# Gagabiro_power_supply_maida.net
KiCad netlist of a schematic drawn in Altium Designer
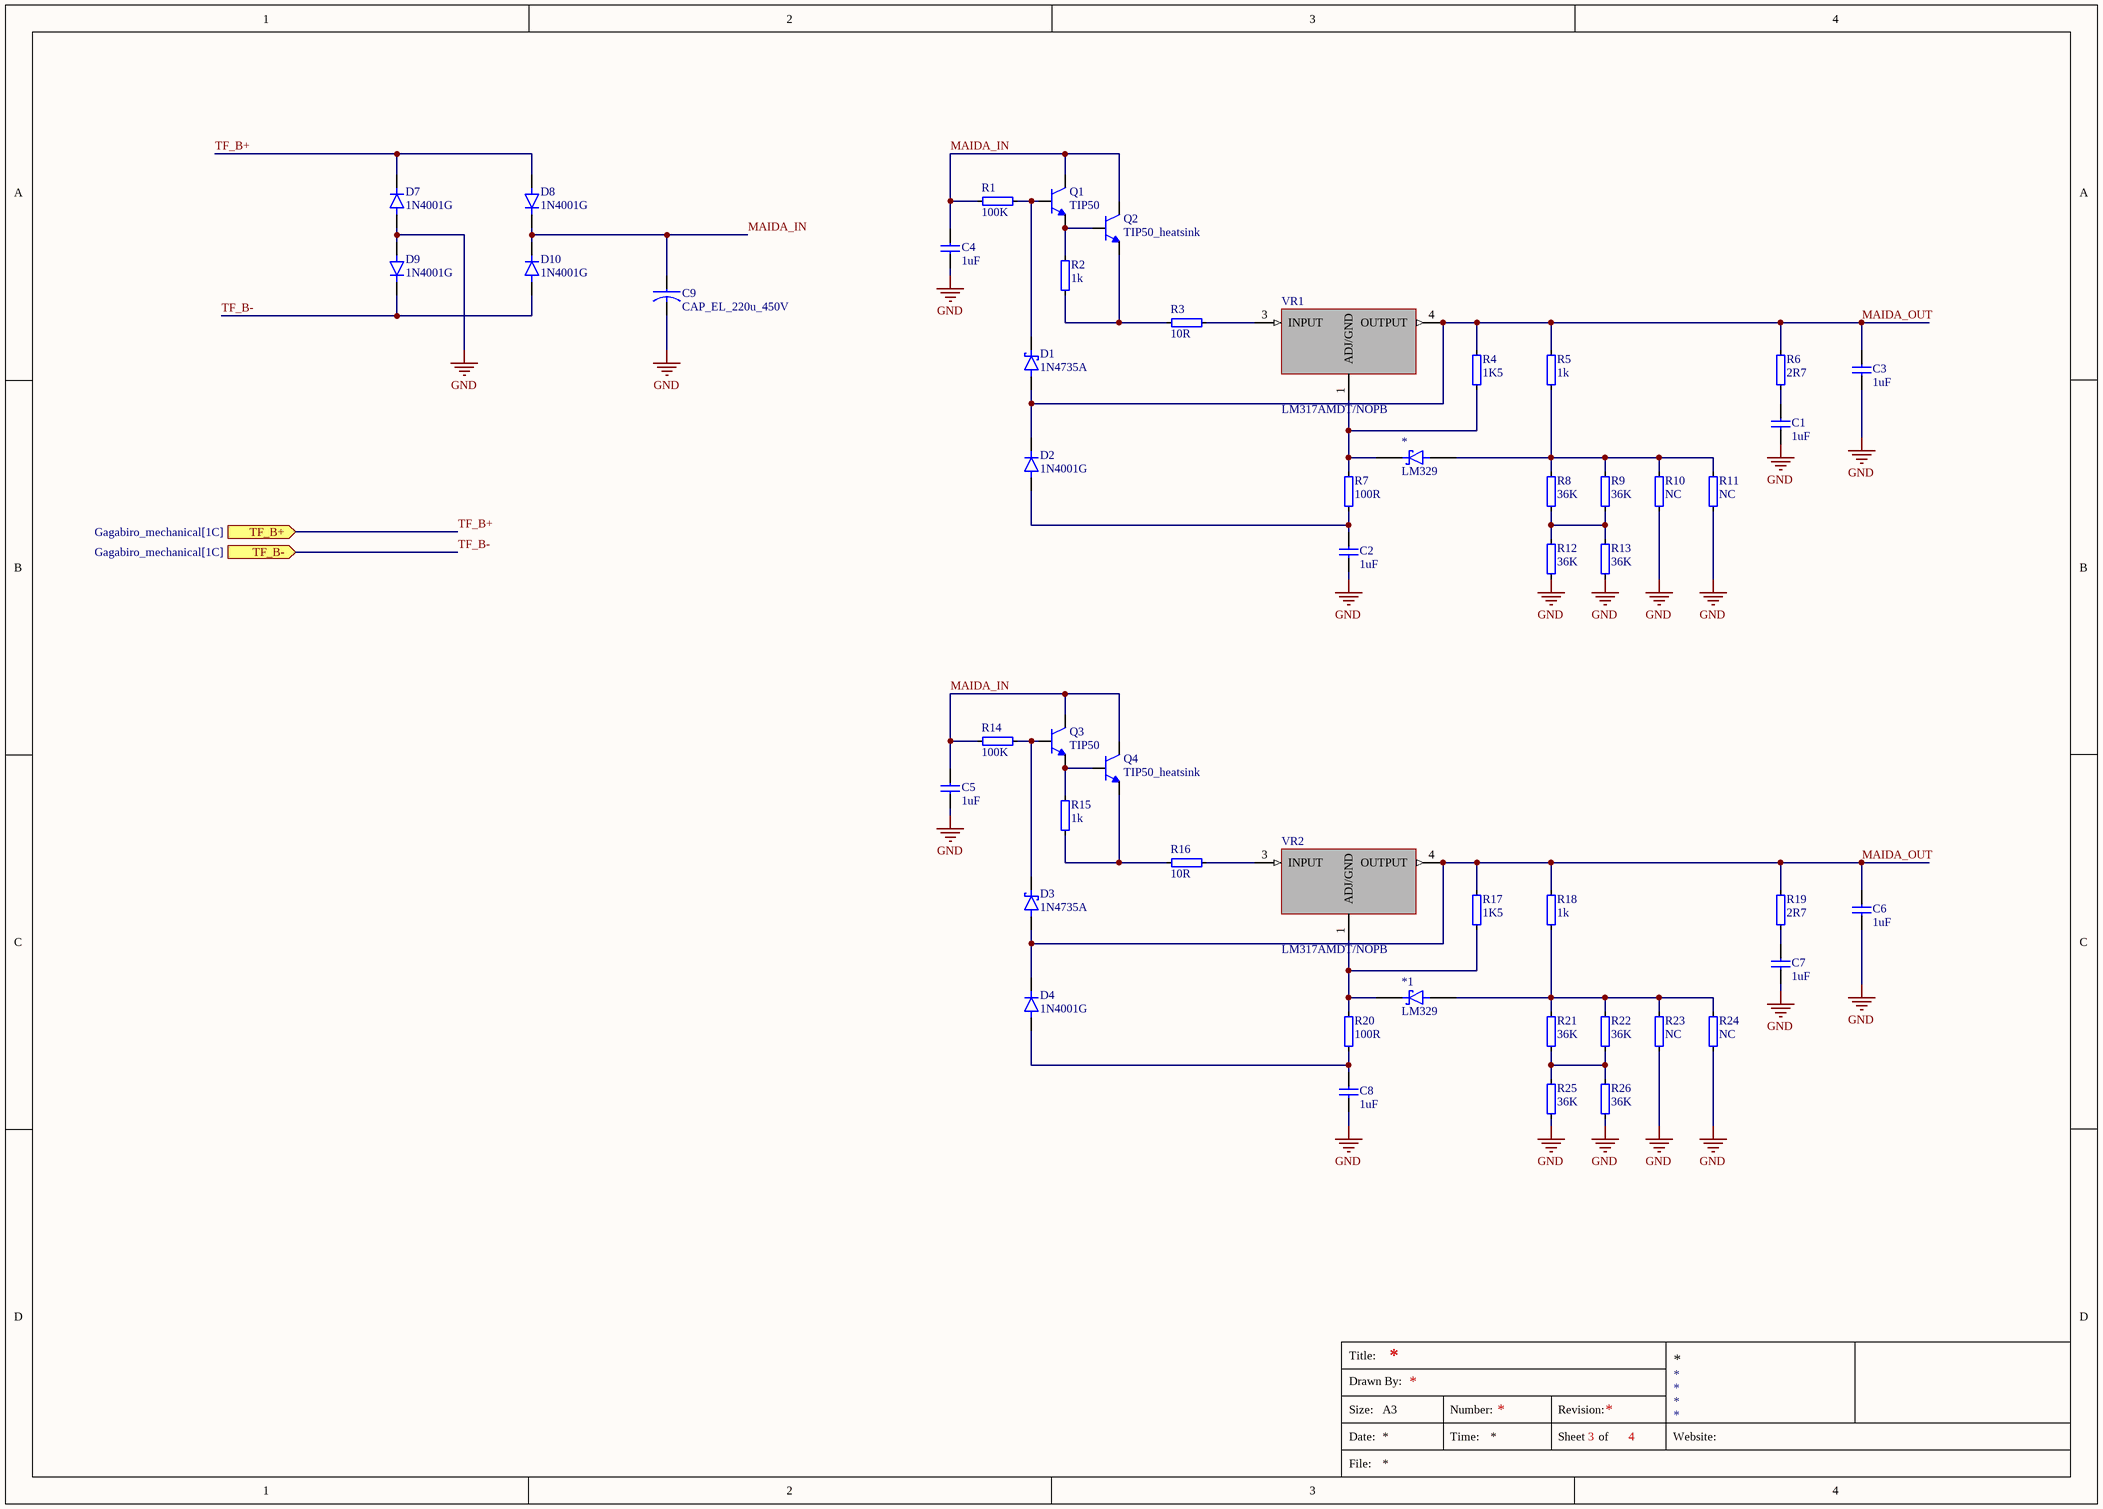
[diagram p0: Gagabiro_power_supply_maida.SchDoc]

(export (version "E")
  (design (tool "Eeschema 10.0.6"))
  (components
    (comp (ref "*")
      (value "LM329")
      (footprint "TO92127P495H495-3")
      (libsource (lib "Persephone_Integrated_Library") (part "LM329"))
    )
    (comp (ref "*1")
      (value "LM329")
      (footprint "TO92127P495H495-3")
      (libsource (lib "Persephone_Integrated_Library") (part "LM329"))
    )
    (comp (ref "C1")
      (value "1uF")
      (footprint "CAP_panassonic_1u_450V")
      (description "Capacitor, Silver Mica")
      (fields (field (name "PART NUMBER") "CMICA_47PF"))
      (libsource (lib "Persephone_Integrated_Library") (part "CAP_POLY_1u"))
    )
    (comp (ref "C2")
      (value "1uF")
      (footprint "CAP_panassonic_1u_450V")
      (description "Capacitor, Silver Mica")
      (fields (field (name "PART NUMBER") "CMICA_47PF"))
      (libsource (lib "Persephone_Integrated_Library") (part "CAP_POLY_1u"))
    )
    (comp (ref "C3")
      (value "1uF")
      (footprint "CAP_panassonic_1u_450V")
      (description "Capacitor, Silver Mica")
      (fields (field (name "PART NUMBER") "CMICA_47PF"))
      (libsource (lib "Persephone_Integrated_Library") (part "CAP_POLY_1u"))
    )
    (comp (ref "C4")
      (value "1uF")
      (footprint "CAP_panassonic_1u_450V")
      (description "Capacitor, Silver Mica")
      (fields (field (name "PART NUMBER") "CMICA_47PF"))
      (libsource (lib "Persephone_Integrated_Library") (part "CAP_POLY_1u"))
    )
    (comp (ref "C5")
      (value "1uF")
      (footprint "CAP_panassonic_1u_450V")
      (description "Capacitor, Silver Mica")
      (fields (field (name "PART NUMBER") "CMICA_47PF"))
      (libsource (lib "Persephone_Integrated_Library") (part "CAP_POLY_1u"))
    )
    (comp (ref "C6")
      (value "1uF")
      (footprint "CAP_panassonic_1u_450V")
      (description "Capacitor, Silver Mica")
      (fields (field (name "PART NUMBER") "CMICA_47PF"))
      (libsource (lib "Persephone_Integrated_Library") (part "CAP_POLY_1u"))
    )
    (comp (ref "C7")
      (value "1uF")
      (footprint "CAP_panassonic_1u_450V")
      (description "Capacitor, Silver Mica")
      (fields (field (name "PART NUMBER") "CMICA_47PF"))
      (libsource (lib "Persephone_Integrated_Library") (part "CAP_POLY_1u"))
    )
    (comp (ref "C8")
      (value "1uF")
      (footprint "CAP_panassonic_1u_450V")
      (description "Capacitor, Silver Mica")
      (fields (field (name "PART NUMBER") "CMICA_47PF"))
      (libsource (lib "Persephone_Integrated_Library") (part "CAP_POLY_1u"))
    )
    (comp (ref "C9")
      (value "CAP_EL_220u_450V")
      (footprint "CAPPRD500W50D630H1120_stand_25x50")
      (description "220F 16V Aluminum Electrolytic Capacitors Radial, Can 1000 Hrs @ 105C")
      (fields (field (name "MP") "EEU-HD1C221B") (field (name "MF") "Panasonic"))
      (libsource (lib "Persephone_Integrated_Library") (part "CAP_EL_220u_450V"))
    )
    (comp (ref "D1")
      (value "1N4735A")
      (footprint "DIOAD1036W78L463D272")
      (description "Zener Diode 6.2V 1W Â±5% Through Hole DO-204AL (DO-41)")
      (fields (field (name "MF") "ON Semiconductor"))
      (libsource (lib "Persephone_Integrated_Library") (part "1N4735A"))
    )
    (comp (ref "D2")
      (value "1N4001G")
      (footprint "DIOAD1036W78L470D235")
      (description "1A, 50V, Standard Recovery Rectifier")
      (fields (field (name "MF") "Taiwan Semiconductor"))
      (libsource (lib "Persephone_Integrated_Library") (part "1N4001G"))
    )
    (comp (ref "D3")
      (value "1N4735A")
      (footprint "DIOAD1036W78L463D272")
      (description "Zener Diode 6.2V 1W Â±5% Through Hole DO-204AL (DO-41)")
      (fields (field (name "MF") "ON Semiconductor"))
      (libsource (lib "Persephone_Integrated_Library") (part "1N4735A"))
    )
    (comp (ref "D4")
      (value "1N4001G")
      (footprint "DIOAD1036W78L470D235")
      (description "1A, 50V, Standard Recovery Rectifier")
      (fields (field (name "MF") "Taiwan Semiconductor"))
      (libsource (lib "Persephone_Integrated_Library") (part "1N4001G"))
    )
    (comp (ref "D7")
      (value "1N4001G")
      (footprint "DIOAD1036W78L470D235")
      (description "1A, 50V, Standard Recovery Rectifier")
      (fields (field (name "MF") "Taiwan Semiconductor"))
      (libsource (lib "Persephone_Integrated_Library") (part "1N4001G"))
    )
    (comp (ref "D8")
      (value "1N4001G")
      (footprint "DIOAD1036W78L470D235")
      (description "1A, 50V, Standard Recovery Rectifier")
      (fields (field (name "MF") "Taiwan Semiconductor"))
      (libsource (lib "Persephone_Integrated_Library") (part "1N4001G"))
    )
    (comp (ref "D9")
      (value "1N4001G")
      (footprint "DIOAD1036W78L470D235")
      (description "1A, 50V, Standard Recovery Rectifier")
      (fields (field (name "MF") "Taiwan Semiconductor"))
      (libsource (lib "Persephone_Integrated_Library") (part "1N4001G"))
    )
    (comp (ref "D10")
      (value "1N4001G")
      (footprint "DIOAD1036W78L470D235")
      (description "1A, 50V, Standard Recovery Rectifier")
      (fields (field (name "MF") "Taiwan Semiconductor"))
      (libsource (lib "Persephone_Integrated_Library") (part "1N4001G"))
    )
    (comp (ref "Q1")
      (value "TIP50")
      (footprint "TO254P1009X445X1985-3")
      (description "Bipolar (BJT) Transistor NPN 400 V 1 A 10MHz 2 W Through Hole TO-220-3")
      (fields (field (name "MF") "ON Semiconductor"))
      (libsource (lib "Persephone_Integrated_Library") (part "TIP50"))
    )
    (comp (ref "Q2")
      (value "TIP50_heatsink")
      (footprint "TO254P1009X445X1985-3_heatsink")
      (description "Bipolar (BJT) Transistor NPN 400 V 1 A 10MHz 2 W Through Hole TO-220-3")
      (fields (field (name "MF") "ON Semiconductor") (field (name "MP") "TIP50"))
      (libsource (lib "Persephone_Integrated_Library") (part "TIP50_heatsink"))
    )
    (comp (ref "Q3")
      (value "TIP50")
      (footprint "TO254P1009X445X1985-3")
      (description "Bipolar (BJT) Transistor NPN 400 V 1 A 10MHz 2 W Through Hole TO-220-3")
      (fields (field (name "MF") "ON Semiconductor"))
      (libsource (lib "Persephone_Integrated_Library") (part "TIP50"))
    )
    (comp (ref "Q4")
      (value "TIP50_heatsink")
      (footprint "TO254P1009X445X1985-3_heatsink")
      (description "Bipolar (BJT) Transistor NPN 400 V 1 A 10MHz 2 W Through Hole TO-220-3")
      (fields (field (name "MF") "ON Semiconductor") (field (name "MP") "TIP50"))
      (libsource (lib "Persephone_Integrated_Library") (part "TIP50_heatsink"))
    )
    (comp (ref "R1")
      (value "100K")
      (footprint "RES_2W_vertical")
      (description "Resistor, 2W")
      (fields (field (name "PART NUMBER") "R2W") (field (name "AUTHOR") "colombari"))
      (libsource (lib "Persephone_Integrated_Library") (part "R_2W_vertical_100K"))
    )
    (comp (ref "R2")
      (value "1k")
      (footprint "RES_2W_vertical")
      (description "Resistor, 2W")
      (fields (field (name "PART NUMBER") "R2W") (field (name "AUTHOR") "colombari"))
      (libsource (lib "Persephone_Integrated_Library") (part "R_2W_vertical_1k"))
    )
    (comp (ref "R3")
      (value "10R")
      (footprint "RES_2W_vertical")
      (description "Resistor, 2W")
      (fields (field (name "PART NUMBER") "R2W") (field (name "AUTHOR") "colombari"))
      (libsource (lib "Persephone_Integrated_Library") (part "R_2W_vertical_10R"))
    )
    (comp (ref "R4")
      (value "1K5")
      (footprint "RES_2W_vertical")
      (description "Resistor, 2W")
      (fields (field (name "PART NUMBER") "R2W") (field (name "AUTHOR") "colombari"))
      (libsource (lib "Persephone_Integrated_Library") (part "R_2W_vertical_1K5"))
    )
    (comp (ref "R5")
      (value "1k")
      (footprint "RES_2W_vertical")
      (description "Resistor, 2W")
      (fields (field (name "PART NUMBER") "R2W") (field (name "AUTHOR") "colombari"))
      (libsource (lib "Persephone_Integrated_Library") (part "R_2W_vertical_1k"))
    )
    (comp (ref "R6")
      (value "2R7")
      (footprint "RES_2W_vertical")
      (description "Resistor, 2W")
      (fields (field (name "PART NUMBER") "R2W") (field (name "AUTHOR") "colombari"))
      (libsource (lib "Persephone_Integrated_Library") (part "R_2W_vertical_2R7"))
    )
    (comp (ref "R7")
      (value "100R")
      (footprint "RES_2W_vertical")
      (description "Resistor, 2W")
      (fields (field (name "PART NUMBER") "R2W") (field (name "AUTHOR") "colombari"))
      (libsource (lib "Persephone_Integrated_Library") (part "R_2W_vertical_100R"))
    )
    (comp (ref "R8")
      (value "36K")
      (footprint "RES_2W_vertical")
      (description "Resistor, 2W")
      (fields (field (name "PART NUMBER") "R2W") (field (name "AUTHOR") "colombari"))
      (libsource (lib "Persephone_Integrated_Library") (part "R_2W_vertical_36K"))
    )
    (comp (ref "R9")
      (value "36K")
      (footprint "RES_2W_vertical")
      (description "Resistor, 2W")
      (fields (field (name "PART NUMBER") "R2W") (field (name "AUTHOR") "colombari"))
      (libsource (lib "Persephone_Integrated_Library") (part "R_2W_vertical_36K"))
    )
    (comp (ref "R10")
      (value "NC")
      (footprint "RES_2W_vertical")
      (description "Resistor, 2W")
      (fields (field (name "PART NUMBER") "R2W") (field (name "AUTHOR") "colombari"))
      (libsource (lib "Persephone_Integrated_Library") (part "R_2W_vertical_NC"))
    )
    (comp (ref "R11")
      (value "NC")
      (footprint "RES_2W_vertical")
      (description "Resistor, 2W")
      (fields (field (name "PART NUMBER") "R2W") (field (name "AUTHOR") "colombari"))
      (libsource (lib "Persephone_Integrated_Library") (part "R_2W_vertical_NC"))
    )
    (comp (ref "R12")
      (value "36K")
      (footprint "RES_2W_vertical")
      (description "Resistor, 2W")
      (fields (field (name "PART NUMBER") "R2W") (field (name "AUTHOR") "colombari"))
      (libsource (lib "Persephone_Integrated_Library") (part "R_2W_vertical_36K"))
    )
    (comp (ref "R13")
      (value "36K")
      (footprint "RES_2W_vertical")
      (description "Resistor, 2W")
      (fields (field (name "PART NUMBER") "R2W") (field (name "AUTHOR") "colombari"))
      (libsource (lib "Persephone_Integrated_Library") (part "R_2W_vertical_36K"))
    )
    (comp (ref "R14")
      (value "100K")
      (footprint "RES_2W_vertical")
      (description "Resistor, 2W")
      (fields (field (name "PART NUMBER") "R2W") (field (name "AUTHOR") "colombari"))
      (libsource (lib "Persephone_Integrated_Library") (part "R_2W_vertical_100K"))
    )
    (comp (ref "R15")
      (value "1k")
      (footprint "RES_2W_vertical")
      (description "Resistor, 2W")
      (fields (field (name "PART NUMBER") "R2W") (field (name "AUTHOR") "colombari"))
      (libsource (lib "Persephone_Integrated_Library") (part "R_2W_vertical_1k"))
    )
    (comp (ref "R16")
      (value "10R")
      (footprint "RES_2W_vertical")
      (description "Resistor, 2W")
      (fields (field (name "PART NUMBER") "R2W") (field (name "AUTHOR") "colombari"))
      (libsource (lib "Persephone_Integrated_Library") (part "R_2W_vertical_10R"))
    )
    (comp (ref "R17")
      (value "1K5")
      (footprint "RES_2W_vertical")
      (description "Resistor, 2W")
      (fields (field (name "PART NUMBER") "R2W") (field (name "AUTHOR") "colombari"))
      (libsource (lib "Persephone_Integrated_Library") (part "R_2W_vertical_1K5"))
    )
    (comp (ref "R18")
      (value "1k")
      (footprint "RES_2W_vertical")
      (description "Resistor, 2W")
      (fields (field (name "PART NUMBER") "R2W") (field (name "AUTHOR") "colombari"))
      (libsource (lib "Persephone_Integrated_Library") (part "R_2W_vertical_1k"))
    )
    (comp (ref "R19")
      (value "2R7")
      (footprint "RES_2W_vertical")
      (description "Resistor, 2W")
      (fields (field (name "PART NUMBER") "R2W") (field (name "AUTHOR") "colombari"))
      (libsource (lib "Persephone_Integrated_Library") (part "R_2W_vertical_2R7"))
    )
    (comp (ref "R20")
      (value "100R")
      (footprint "RES_2W_vertical")
      (description "Resistor, 2W")
      (fields (field (name "PART NUMBER") "R2W") (field (name "AUTHOR") "colombari"))
      (libsource (lib "Persephone_Integrated_Library") (part "R_2W_vertical_100R"))
    )
    (comp (ref "R21")
      (value "36K")
      (footprint "RES_2W_vertical")
      (description "Resistor, 2W")
      (fields (field (name "PART NUMBER") "R2W") (field (name "AUTHOR") "colombari"))
      (libsource (lib "Persephone_Integrated_Library") (part "R_2W_vertical_36K"))
    )
    (comp (ref "R22")
      (value "36K")
      (footprint "RES_2W_vertical")
      (description "Resistor, 2W")
      (fields (field (name "PART NUMBER") "R2W") (field (name "AUTHOR") "colombari"))
      (libsource (lib "Persephone_Integrated_Library") (part "R_2W_vertical_36K"))
    )
    (comp (ref "R23")
      (value "NC")
      (footprint "RES_2W_vertical")
      (description "Resistor, 2W")
      (fields (field (name "PART NUMBER") "R2W") (field (name "AUTHOR") "colombari"))
      (libsource (lib "Persephone_Integrated_Library") (part "R_2W_vertical_NC"))
    )
    (comp (ref "R24")
      (value "NC")
      (footprint "RES_2W_vertical")
      (description "Resistor, 2W")
      (fields (field (name "PART NUMBER") "R2W") (field (name "AUTHOR") "colombari"))
      (libsource (lib "Persephone_Integrated_Library") (part "R_2W_vertical_NC"))
    )
    (comp (ref "R25")
      (value "36K")
      (footprint "RES_2W_vertical")
      (description "Resistor, 2W")
      (fields (field (name "PART NUMBER") "R2W") (field (name "AUTHOR") "colombari"))
      (libsource (lib "Persephone_Integrated_Library") (part "R_2W_vertical_36K"))
    )
    (comp (ref "R26")
      (value "36K")
      (footprint "RES_2W_vertical")
      (description "Resistor, 2W")
      (fields (field (name "PART NUMBER") "R2W") (field (name "AUTHOR") "colombari"))
      (libsource (lib "Persephone_Integrated_Library") (part "R_2W_vertical_36K"))
    )
    (comp (ref "VR1")
      (value "LM317AMDT/NOPB")
      (footprint "TO228P991X255-3N")
      (libsource (lib "Persephone_Integrated_Library") (part "LM317AMDT/NOPB"))
    )
    (comp (ref "VR2")
      (value "LM317AMDT/NOPB")
      (footprint "TO228P991X255-3N")
      (libsource (lib "Persephone_Integrated_Library") (part "LM317AMDT/NOPB"))
    )
  )
  (nets
    (net (code "1") (name "/MAIDA_IN") (class "Default")
      (node (ref "C4") (pin "2") (pinfunction "2_2") (pintype "passive"))
      (node (ref "C5") (pin "2") (pinfunction "2_2") (pintype "passive"))
      (node (ref "C9") (pin "P") (pinfunction "P_P") (pintype "passive"))
      (node (ref "D10") (pin "C") (pinfunction "K_C") (pintype "passive"))
      (node (ref "D8") (pin "C") (pinfunction "K_C") (pintype "passive"))
      (node (ref "Q1") (pin "2") (pinfunction "C_2") (pintype "passive"))
      (node (ref "Q2") (pin "2") (pinfunction "C_2") (pintype "passive"))
      (node (ref "Q3") (pin "2") (pinfunction "C_2") (pintype "passive"))
      (node (ref "Q4") (pin "2") (pinfunction "C_2") (pintype "passive"))
      (node (ref "R1") (pin "1") (pinfunction "1_1") (pintype "passive"))
      (node (ref "R14") (pin "1") (pinfunction "1_1") (pintype "passive"))
    )
    (net (code "2") (name "/MAIDA_OUT") (class "Default")
      (node (ref "C3") (pin "2") (pinfunction "2_2") (pintype "passive"))
      (node (ref "C6") (pin "2") (pinfunction "2_2") (pintype "passive"))
      (node (ref "D1") (pin "2") (pinfunction "A_2") (pintype "passive"))
      (node (ref "D2") (pin "C") (pinfunction "K_C") (pintype "passive"))
      (node (ref "D3") (pin "2") (pinfunction "A_2") (pintype "passive"))
      (node (ref "D4") (pin "C") (pinfunction "K_C") (pintype "passive"))
      (node (ref "R17") (pin "2") (pinfunction "2_2") (pintype "passive"))
      (node (ref "R18") (pin "2") (pinfunction "2_2") (pintype "passive"))
      (node (ref "R19") (pin "2") (pinfunction "2_2") (pintype "passive"))
      (node (ref "R4") (pin "2") (pinfunction "2_2") (pintype "passive"))
      (node (ref "R5") (pin "2") (pinfunction "2_2") (pintype "passive"))
      (node (ref "R6") (pin "2") (pinfunction "2_2") (pintype "passive"))
      (node (ref "VR1") (pin "4") (pinfunction "OUTPUT_4") (pintype "output"))
      (node (ref "VR2") (pin "4") (pinfunction "OUTPUT_4") (pintype "output"))
    )
    (net (code "3") (name "/TF_B+") (class "Default")
      (node (ref "D7") (pin "C") (pinfunction "K_C") (pintype "passive"))
      (node (ref "D8") (pin "A") (pinfunction "A_A") (pintype "passive"))
    )
    (net (code "4") (name "/TF_B-") (class "Default")
      (node (ref "D10") (pin "A") (pinfunction "A_A") (pintype "passive"))
      (node (ref "D9") (pin "C") (pinfunction "K_C") (pintype "passive"))
    )
    (net (code "5") (name "GND") (class "Default")
      (node (ref "C1") (pin "1") (pinfunction "1_1") (pintype "passive"))
      (node (ref "C2") (pin "1") (pinfunction "1_1") (pintype "passive"))
      (node (ref "C3") (pin "1") (pinfunction "1_1") (pintype "passive"))
      (node (ref "C4") (pin "1") (pinfunction "1_1") (pintype "passive"))
      (node (ref "C5") (pin "1") (pinfunction "1_1") (pintype "passive"))
      (node (ref "C6") (pin "1") (pinfunction "1_1") (pintype "passive"))
      (node (ref "C7") (pin "1") (pinfunction "1_1") (pintype "passive"))
      (node (ref "C8") (pin "1") (pinfunction "1_1") (pintype "passive"))
      (node (ref "C9") (pin "N") (pinfunction "N_N") (pintype "passive"))
      (node (ref "D7") (pin "A") (pinfunction "A_A") (pintype "passive"))
      (node (ref "D9") (pin "A") (pinfunction "A_A") (pintype "passive"))
      (node (ref "R10") (pin "1") (pinfunction "1_1") (pintype "passive"))
      (node (ref "R11") (pin "1") (pinfunction "1_1") (pintype "passive"))
      (node (ref "R12") (pin "1") (pinfunction "1_1") (pintype "passive"))
      (node (ref "R13") (pin "1") (pinfunction "1_1") (pintype "passive"))
      (node (ref "R23") (pin "1") (pinfunction "1_1") (pintype "passive"))
      (node (ref "R24") (pin "1") (pinfunction "1_1") (pintype "passive"))
      (node (ref "R25") (pin "1") (pinfunction "1_1") (pintype "passive"))
      (node (ref "R26") (pin "1") (pinfunction "1_1") (pintype "passive"))
    )
    (net (code "6") (name "Net-(*-Pad3)") (class "Default")
      (node (ref "*") (pin "3") (pinfunction "3_3") (pintype "power_in"))
      (node (ref "R10") (pin "2") (pinfunction "2_2") (pintype "passive"))
      (node (ref "R11") (pin "2") (pinfunction "2_2") (pintype "passive"))
      (node (ref "R5") (pin "1") (pinfunction "1_1") (pintype "passive"))
      (node (ref "R8") (pin "2") (pinfunction "2_2") (pintype "passive"))
      (node (ref "R9") (pin "2") (pinfunction "2_2") (pintype "passive"))
    )
    (net (code "7") (name "Net-(*1-Pad3)") (class "Default")
      (node (ref "*1") (pin "3") (pinfunction "3_3") (pintype "power_in"))
      (node (ref "R18") (pin "1") (pinfunction "1_1") (pintype "passive"))
      (node (ref "R21") (pin "2") (pinfunction "2_2") (pintype "passive"))
      (node (ref "R22") (pin "2") (pinfunction "2_2") (pintype "passive"))
      (node (ref "R23") (pin "2") (pinfunction "2_2") (pintype "passive"))
      (node (ref "R24") (pin "2") (pinfunction "2_2") (pintype "passive"))
    )
    (net (code "8") (name "Net-(C1-Pad2)") (class "Default")
      (node (ref "C1") (pin "2") (pinfunction "2_2") (pintype "passive"))
      (node (ref "R6") (pin "1") (pinfunction "1_1") (pintype "passive"))
    )
    (net (code "9") (name "Net-(C2-Pad2)") (class "Default")
      (node (ref "C2") (pin "2") (pinfunction "2_2") (pintype "passive"))
      (node (ref "D2") (pin "A") (pinfunction "A_A") (pintype "passive"))
      (node (ref "R7") (pin "1") (pinfunction "1_1") (pintype "passive"))
    )
    (net (code "10") (name "Net-(C7-Pad2)") (class "Default")
      (node (ref "C7") (pin "2") (pinfunction "2_2") (pintype "passive"))
      (node (ref "R19") (pin "1") (pinfunction "1_1") (pintype "passive"))
    )
    (net (code "11") (name "Net-(C8-Pad2)") (class "Default")
      (node (ref "C8") (pin "2") (pinfunction "2_2") (pintype "passive"))
      (node (ref "D4") (pin "A") (pinfunction "A_A") (pintype "passive"))
      (node (ref "R20") (pin "1") (pinfunction "1_1") (pintype "passive"))
    )
    (net (code "12") (name "Net-(D1-K)") (class "Default")
      (node (ref "D1") (pin "1") (pinfunction "K_1") (pintype "passive"))
      (node (ref "Q1") (pin "1") (pinfunction "B_1") (pintype "passive"))
      (node (ref "R1") (pin "2") (pinfunction "2_2") (pintype "passive"))
    )
    (net (code "13") (name "Net-(D3-K)") (class "Default")
      (node (ref "D3") (pin "1") (pinfunction "K_1") (pintype "passive"))
      (node (ref "Q3") (pin "1") (pinfunction "B_1") (pintype "passive"))
      (node (ref "R14") (pin "2") (pinfunction "2_2") (pintype "passive"))
    )
    (net (code "14") (name "Net-(Q1-E)") (class "Default")
      (node (ref "Q1") (pin "3") (pinfunction "E_3") (pintype "passive"))
      (node (ref "Q2") (pin "1") (pinfunction "B_1") (pintype "passive"))
      (node (ref "R2") (pin "2") (pinfunction "2_2") (pintype "passive"))
    )
    (net (code "15") (name "Net-(Q2-E)") (class "Default")
      (node (ref "Q2") (pin "3") (pinfunction "E_3") (pintype "passive"))
      (node (ref "R2") (pin "1") (pinfunction "1_1") (pintype "passive"))
      (node (ref "R3") (pin "2") (pinfunction "2_2") (pintype "passive"))
    )
    (net (code "16") (name "Net-(Q3-E)") (class "Default")
      (node (ref "Q3") (pin "3") (pinfunction "E_3") (pintype "passive"))
      (node (ref "Q4") (pin "1") (pinfunction "B_1") (pintype "passive"))
      (node (ref "R15") (pin "2") (pinfunction "2_2") (pintype "passive"))
    )
    (net (code "17") (name "Net-(Q4-E)") (class "Default")
      (node (ref "Q4") (pin "3") (pinfunction "E_3") (pintype "passive"))
      (node (ref "R15") (pin "1") (pinfunction "1_1") (pintype "passive"))
      (node (ref "R16") (pin "2") (pinfunction "2_2") (pintype "passive"))
    )
    (net (code "18") (name "Net-(R12-Pad2)") (class "Default")
      (node (ref "R12") (pin "2") (pinfunction "2_2") (pintype "passive"))
      (node (ref "R13") (pin "2") (pinfunction "2_2") (pintype "passive"))
      (node (ref "R8") (pin "1") (pinfunction "1_1") (pintype "passive"))
      (node (ref "R9") (pin "1") (pinfunction "1_1") (pintype "passive"))
    )
    (net (code "19") (name "Net-(R21-Pad1)") (class "Default")
      (node (ref "R21") (pin "1") (pinfunction "1_1") (pintype "passive"))
      (node (ref "R22") (pin "1") (pinfunction "1_1") (pintype "passive"))
      (node (ref "R25") (pin "2") (pinfunction "2_2") (pintype "passive"))
      (node (ref "R26") (pin "2") (pinfunction "2_2") (pintype "passive"))
    )
    (net (code "20") (name "Net-(VR1-ADJ{slash}GND)") (class "Default")
      (node (ref "*") (pin "2") (pinfunction "2_2") (pintype "power_in"))
      (node (ref "R4") (pin "1") (pinfunction "1_1") (pintype "passive"))
      (node (ref "R7") (pin "2") (pinfunction "2_2") (pintype "passive"))
      (node (ref "VR1") (pin "1") (pinfunction "ADJ/GND_1") (pintype "power_in"))
    )
    (net (code "21") (name "Net-(VR1-INPUT)") (class "Default")
      (node (ref "R3") (pin "1") (pinfunction "1_1") (pintype "passive"))
      (node (ref "VR1") (pin "3") (pinfunction "INPUT_3") (pintype "input"))
    )
    (net (code "22") (name "Net-(VR2-ADJ{slash}GND)") (class "Default")
      (node (ref "*1") (pin "2") (pinfunction "2_2") (pintype "power_in"))
      (node (ref "R17") (pin "1") (pinfunction "1_1") (pintype "passive"))
      (node (ref "R20") (pin "2") (pinfunction "2_2") (pintype "passive"))
      (node (ref "VR2") (pin "1") (pinfunction "ADJ/GND_1") (pintype "power_in"))
    )
    (net (code "23") (name "Net-(VR2-INPUT)") (class "Default")
      (node (ref "R16") (pin "1") (pinfunction "1_1") (pintype "passive"))
      (node (ref "VR2") (pin "3") (pinfunction "INPUT_3") (pintype "input"))
    )
  )
)
